# MCU_IO.net
KiCad netlist of a schematic drawn in Altium Designer
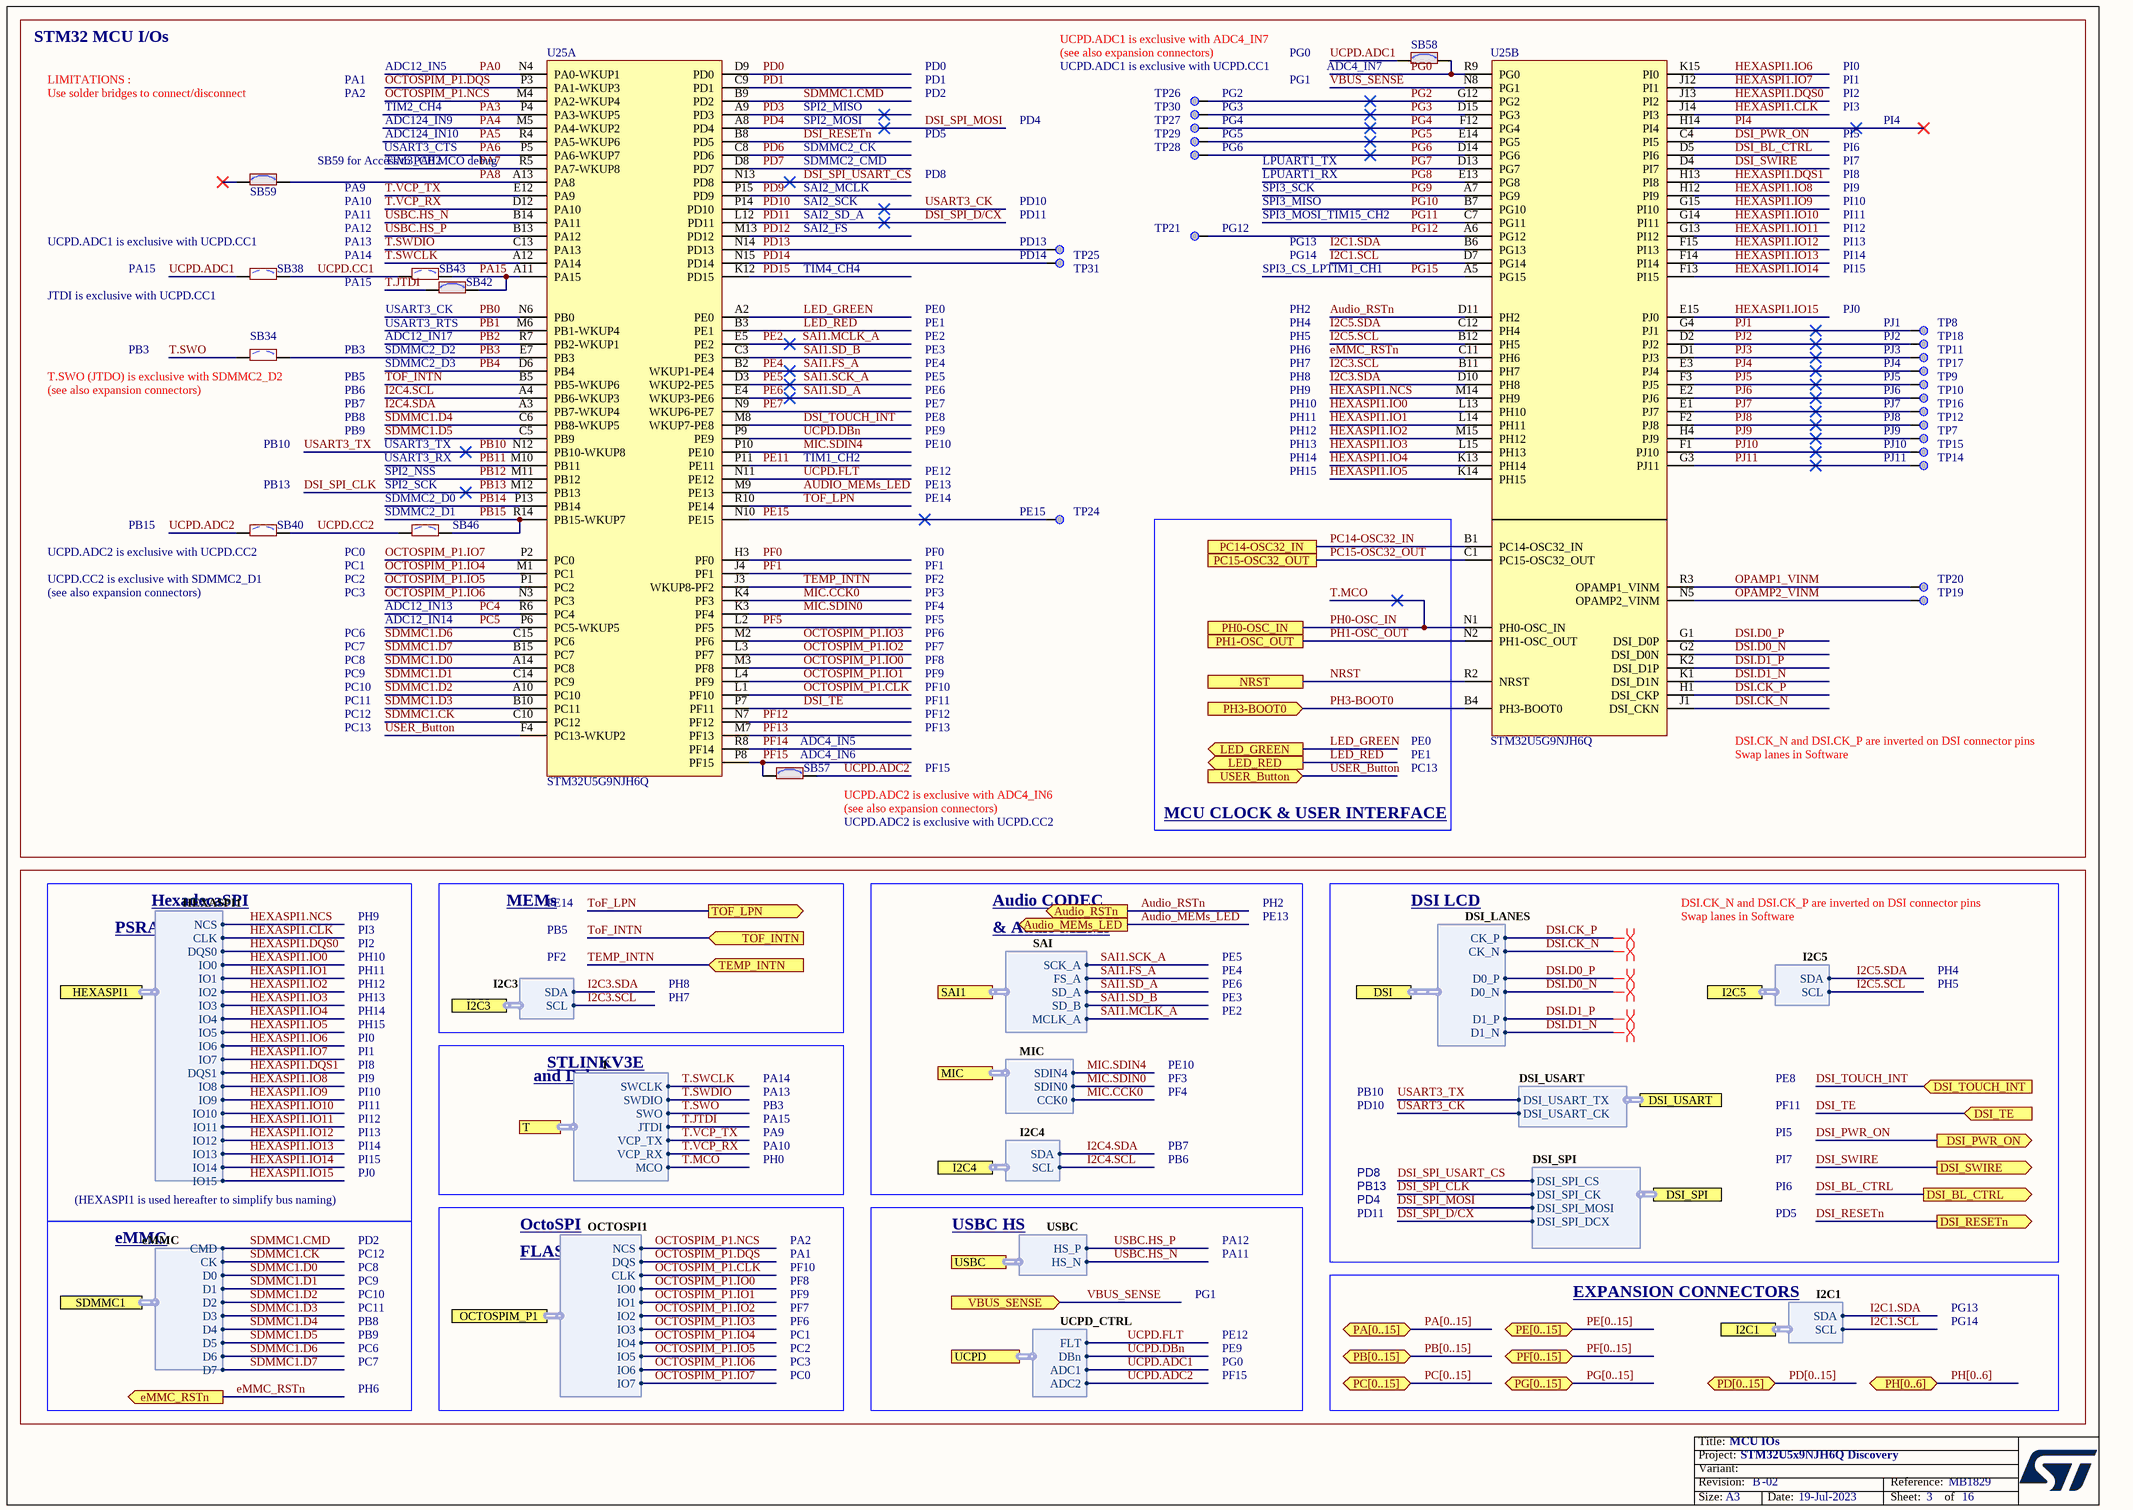
[diagram p0: MCU_IO.SchDoc]

(export (version "E")
  (design (tool "Eeschema 10.0.6"))
  (components
    (comp (ref "SB34")
      (value "SB_OFF")
      (footprint "MCD_PARTS:SOLDER-BRIDGE_R0402-0R")
      (description "Solder Bridge 0402 OFF")
      (fields
        (field (name "INTERNAL_PART_NUMBER") "MCD-02162")
        (field (name "MANUFACTURER_PART_NUMBER") "RC0402JR-070RL")
      )
      (libsource (lib "MCD_PARTS_database") (part "SB_OFF"))
    )
    (comp (ref "SB38")
      (value "SB_OFF")
      (footprint "MCD_PARTS:SOLDER-BRIDGE_R0402-0R")
      (description "Solder Bridge 0402 OFF")
      (fields
        (field (name "INTERNAL_PART_NUMBER") "MCD-02162")
        (field (name "MANUFACTURER_PART_NUMBER") "RC0402JR-070RL")
      )
      (libsource (lib "MCD_PARTS_database") (part "SB_OFF"))
    )
    (comp (ref "SB40")
      (value "SB_OFF")
      (footprint "MCD_PARTS:SOLDER-BRIDGE_R0402-0R")
      (description "Solder Bridge 0402 OFF")
      (fields
        (field (name "INTERNAL_PART_NUMBER") "MCD-02162")
        (field (name "MANUFACTURER_PART_NUMBER") "RC0402JR-070RL")
      )
      (libsource (lib "MCD_PARTS_database") (part "SB_OFF"))
    )
    (comp (ref "SB42")
      (value "SB_ON")
      (footprint "MCD_PARTS:SOLDER-BRIDGE_R0402-0R")
      (description "Solder Bridge 0402 ON")
      (fields
        (field (name "INTERNAL_PART_NUMBER") "MCD-01618")
        (field (name "MANUFACTURER_PART_NUMBER") "RC0402JR-070RL")
      )
      (libsource (lib "MCD_PARTS_database") (part "SB_ON"))
    )
    (comp (ref "SB43")
      (value "SB_OFF")
      (footprint "MCD_PARTS:SOLDER-BRIDGE_R0402-0R")
      (description "Solder Bridge 0402 OFF")
      (fields
        (field (name "INTERNAL_PART_NUMBER") "MCD-02162")
        (field (name "MANUFACTURER_PART_NUMBER") "RC0402JR-070RL")
      )
      (libsource (lib "MCD_PARTS_database") (part "SB_OFF"))
    )
    (comp (ref "SB46")
      (value "SB_OFF")
      (footprint "MCD_PARTS:SOLDER-BRIDGE_R0402-0R")
      (description "Solder Bridge 0402 OFF")
      (fields
        (field (name "INTERNAL_PART_NUMBER") "MCD-02162")
        (field (name "MANUFACTURER_PART_NUMBER") "RC0402JR-070RL")
      )
      (libsource (lib "MCD_PARTS_database") (part "SB_OFF"))
    )
    (comp (ref "SB57")
      (value "SB_ON")
      (footprint "MCD_PARTS:SOLDER-BRIDGE_R0402-0R")
      (description "Solder Bridge 0402 ON")
      (fields
        (field (name "INTERNAL_PART_NUMBER") "MCD-01618")
        (field (name "MANUFACTURER_PART_NUMBER") "RC0402JR-070RL")
      )
      (libsource (lib "MCD_PARTS_database") (part "SB_ON"))
    )
    (comp (ref "SB58")
      (value "SB_ON")
      (footprint "MCD_PARTS:SOLDER-BRIDGE_R0402-0R")
      (description "Solder Bridge 0402 ON")
      (fields
        (field (name "INTERNAL_PART_NUMBER") "MCD-01618")
        (field (name "MANUFACTURER_PART_NUMBER") "RC0402JR-070RL")
      )
      (libsource (lib "MCD_PARTS_database") (part "SB_ON"))
    )
    (comp (ref "SB59")
      (value "SB_ON")
      (footprint "MCD_PARTS:SOLDER-BRIDGE_R0402-0R")
      (description "Solder Bridge 0402 ON")
      (fields
        (field (name "INTERNAL_PART_NUMBER") "MCD-01618")
        (field (name "MANUFACTURER_PART_NUMBER") "RC0402JR-070RL")
      )
      (libsource (lib "MCD_PARTS_database") (part "SB_ON"))
    )
    (comp (ref "TP7")
      (value "Test Point")
      (footprint "MCD_PARTS:TP_SMD_1MM")
      (description "Test Point 1mm")
      (fields (field (name "INTERNAL_PART_NUMBER") "MCD-00074"))
      (libsource (lib "MCD_PARTS_database") (part "Test Point"))
    )
    (comp (ref "TP8")
      (value "Test Point")
      (footprint "MCD_PARTS:TP_SMD_1MM")
      (description "Test Point 1mm")
      (fields (field (name "INTERNAL_PART_NUMBER") "MCD-00074"))
      (libsource (lib "MCD_PARTS_database") (part "Test Point"))
    )
    (comp (ref "TP9")
      (value "Test Point")
      (footprint "MCD_PARTS:TP_SMD_1MM")
      (description "Test Point 1mm")
      (fields (field (name "INTERNAL_PART_NUMBER") "MCD-00074"))
      (libsource (lib "MCD_PARTS_database") (part "Test Point"))
    )
    (comp (ref "TP10")
      (value "Test Point")
      (footprint "MCD_PARTS:TP_SMD_1MM")
      (description "Test Point 1mm")
      (fields (field (name "INTERNAL_PART_NUMBER") "MCD-00074"))
      (libsource (lib "MCD_PARTS_database") (part "Test Point"))
    )
    (comp (ref "TP11")
      (value "Test Point")
      (footprint "MCD_PARTS:TP_SMD_1MM")
      (description "Test Point 1mm")
      (fields (field (name "INTERNAL_PART_NUMBER") "MCD-00074"))
      (libsource (lib "MCD_PARTS_database") (part "Test Point"))
    )
    (comp (ref "TP12")
      (value "Test Point")
      (footprint "MCD_PARTS:TP_SMD_1MM")
      (description "Test Point 1mm")
      (fields (field (name "INTERNAL_PART_NUMBER") "MCD-00074"))
      (libsource (lib "MCD_PARTS_database") (part "Test Point"))
    )
    (comp (ref "TP14")
      (value "Test Point")
      (footprint "MCD_PARTS:TP_SMD_1MM")
      (description "Test Point 1mm")
      (fields (field (name "INTERNAL_PART_NUMBER") "MCD-00074"))
      (libsource (lib "MCD_PARTS_database") (part "Test Point"))
    )
    (comp (ref "TP15")
      (value "Test Point")
      (footprint "MCD_PARTS:TP_SMD_1MM")
      (description "Test Point 1mm")
      (fields (field (name "INTERNAL_PART_NUMBER") "MCD-00074"))
      (libsource (lib "MCD_PARTS_database") (part "Test Point"))
    )
    (comp (ref "TP16")
      (value "Test Point")
      (footprint "MCD_PARTS:TP_SMD_1MM")
      (description "Test Point 1mm")
      (fields (field (name "INTERNAL_PART_NUMBER") "MCD-00074"))
      (libsource (lib "MCD_PARTS_database") (part "Test Point"))
    )
    (comp (ref "TP17")
      (value "Test Point")
      (footprint "MCD_PARTS:TP_SMD_1MM")
      (description "Test Point 1mm")
      (fields (field (name "INTERNAL_PART_NUMBER") "MCD-00074"))
      (libsource (lib "MCD_PARTS_database") (part "Test Point"))
    )
    (comp (ref "TP18")
      (value "Test Point")
      (footprint "MCD_PARTS:TP_SMD_1MM")
      (description "Test Point 1mm")
      (fields (field (name "INTERNAL_PART_NUMBER") "MCD-00074"))
      (libsource (lib "MCD_PARTS_database") (part "Test Point"))
    )
    (comp (ref "TP19")
      (value "Test Point")
      (footprint "MCD_PARTS:TP_SMD_1MM")
      (description "Test Point 1mm")
      (fields (field (name "INTERNAL_PART_NUMBER") "MCD-00074"))
      (libsource (lib "MCD_PARTS_database") (part "Test Point"))
    )
    (comp (ref "TP20")
      (value "Test Point")
      (footprint "MCD_PARTS:TP_SMD_1MM")
      (description "Test Point 1mm")
      (fields (field (name "INTERNAL_PART_NUMBER") "MCD-00074"))
      (libsource (lib "MCD_PARTS_database") (part "Test Point"))
    )
    (comp (ref "TP21")
      (value "Test Point")
      (footprint "MCD_PARTS:TP_SMD_1MM")
      (description "Test Point 1mm")
      (fields (field (name "INTERNAL_PART_NUMBER") "MCD-00074"))
      (libsource (lib "") (part "Test Point_1"))
    )
    (comp (ref "TP24")
      (value "Test Point")
      (footprint "MCD_PARTS:TP_SMD_1MM")
      (description "Test Point 1mm")
      (fields (field (name "INTERNAL_PART_NUMBER") "MCD-00074"))
      (libsource (lib "MCD_PARTS_database") (part "Test Point"))
    )
    (comp (ref "TP25")
      (value "Test Point")
      (footprint "MCD_PARTS:TP_SMD_1MM")
      (description "Test Point 1mm")
      (fields (field (name "INTERNAL_PART_NUMBER") "MCD-00074"))
      (libsource (lib "MCD_PARTS_database") (part "Test Point"))
    )
    (comp (ref "TP26")
      (value "Test Point")
      (footprint "MCD_PARTS:TP_SMD_1MM")
      (description "Test Point 1mm")
      (fields (field (name "INTERNAL_PART_NUMBER") "MCD-00074"))
      (libsource (lib "") (part "Test Point_1"))
    )
    (comp (ref "TP27")
      (value "Test Point")
      (footprint "MCD_PARTS:TP_SMD_1MM")
      (description "Test Point 1mm")
      (fields (field (name "INTERNAL_PART_NUMBER") "MCD-00074"))
      (libsource (lib "") (part "Test Point_1"))
    )
    (comp (ref "TP28")
      (value "Test Point")
      (footprint "MCD_PARTS:TP_SMD_1MM")
      (description "Test Point 1mm")
      (fields (field (name "INTERNAL_PART_NUMBER") "MCD-00074"))
      (libsource (lib "") (part "Test Point_1"))
    )
    (comp (ref "TP29")
      (value "Test Point")
      (footprint "MCD_PARTS:TP_SMD_1MM")
      (description "Test Point 1mm")
      (fields (field (name "INTERNAL_PART_NUMBER") "MCD-00074"))
      (libsource (lib "") (part "Test Point_1"))
    )
    (comp (ref "TP30")
      (value "Test Point")
      (footprint "MCD_PARTS:TP_SMD_1MM")
      (description "Test Point 1mm")
      (fields (field (name "INTERNAL_PART_NUMBER") "MCD-00074"))
      (libsource (lib "") (part "Test Point_1"))
    )
    (comp (ref "TP31")
      (value "Test Point")
      (footprint "MCD_PARTS:TP_SMD_1MM")
      (description "Test Point 1mm")
      (fields (field (name "INTERNAL_PART_NUMBER") "MCD-00074"))
      (libsource (lib "MCD_PARTS_database") (part "Test Point"))
    )
    (comp (ref "U25")
      (value "STM32U5G9NJH6Q")
      (footprint "ICC_TFBGA216_13X13_P080_H1P10_CODE-A0L2")
      (description "MCU, ARM Cortex-M33, 4MB Flash, 3MB RAM, With Crypto")
      (fields
        (field (name "INTERNAL_PART_NUMBER") "MCD-03271")
        (field (name "MANUFACTURER") "STMICROELECTRONICS")
      )
      (libsource (lib "MCD_PARTS_database") (part "STM32U599NJH6Q_BGA216_SMPS"))
    )
  )
  (nets
    (net (code "74") (name "/AUDIO_MEMs_LED") (class "Default")
      (node (ref "U25") (pin "M9") (pinfunction "PE13_M9") (pintype "passive"))
    )
    (net (code "76") (name "/Audio_RSTn") (class "Default")
      (node (ref "U25") (pin "D11") (pinfunction "PH2_D11") (pintype "passive"))
    )
    (net (code "77") (name "/DSI.CK_N") (class "Default")
      (node (ref "U25") (pin "J1") (pinfunction "DSI_CKN_J1") (pintype "passive"))
    )
    (net (code "78") (name "/DSI.CK_P") (class "Default")
      (node (ref "U25") (pin "H1") (pinfunction "DSI_CKP_H1") (pintype "passive"))
    )
    (net (code "79") (name "/DSI.D0_N") (class "Default")
      (node (ref "U25") (pin "G2") (pinfunction "DSI_D0N_G2") (pintype "passive"))
    )
    (net (code "80") (name "/DSI.D0_P") (class "Default")
      (node (ref "U25") (pin "G1") (pinfunction "DSI_D0P_G1") (pintype "passive"))
    )
    (net (code "81") (name "/DSI.D1_N") (class "Default")
      (node (ref "U25") (pin "K1") (pinfunction "DSI_D1N_K1") (pintype "passive"))
    )
    (net (code "82") (name "/DSI.D1_P") (class "Default")
      (node (ref "U25") (pin "K2") (pinfunction "DSI_D1P_K2") (pintype "passive"))
    )
    (net (code "83") (name "/DSI_BL_CTRL") (class "Default")
      (node (ref "U25") (pin "D5") (pinfunction "PI6_D5") (pintype "passive"))
    )
    (net (code "84") (name "/DSI_PWR_ON") (class "Default")
      (node (ref "U25") (pin "C4") (pinfunction "PI5_C4") (pintype "passive"))
    )
    (net (code "85") (name "/DSI_RESETn") (class "Default")
      (node (ref "U25") (pin "B8") (pinfunction "PD5_B8") (pintype "passive"))
    )
    (net (code "86") (name "/DSI_SPI_USART_CS") (class "Default")
      (node (ref "U25") (pin "N13") (pinfunction "PD8_N13") (pintype "passive"))
    )
    (net (code "87") (name "/DSI_SWIRE") (class "Default")
      (node (ref "U25") (pin "D4") (pinfunction "PI7_D4") (pintype "passive"))
    )
    (net (code "88") (name "/DSI_TE") (class "Default")
      (node (ref "U25") (pin "P7") (pinfunction "PF11_P7") (pintype "passive"))
    )
    (net (code "89") (name "/DSI_TOUCH_INT") (class "Default")
      (node (ref "U25") (pin "M8") (pinfunction "WKUP7-PE8_M8") (pintype "passive"))
    )
    (net (code "90") (name "/HEXASPI1.CLK") (class "Default")
      (node (ref "U25") (pin "J14") (pinfunction "PI3_J14") (pintype "passive"))
    )
    (net (code "91") (name "/HEXASPI1.DQS0") (class "Default")
      (node (ref "U25") (pin "J13") (pinfunction "PI2_J13") (pintype "passive"))
    )
    (net (code "92") (name "/HEXASPI1.DQS1") (class "Default")
      (node (ref "U25") (pin "H13") (pinfunction "PI8_H13") (pintype "passive"))
    )
    (net (code "93") (name "/HEXASPI1.IO0") (class "Default")
      (node (ref "U25") (pin "L13") (pinfunction "PH10_L13") (pintype "passive"))
    )
    (net (code "94") (name "/HEXASPI1.IO1") (class "Default")
      (node (ref "U25") (pin "L14") (pinfunction "PH11_L14") (pintype "passive"))
    )
    (net (code "95") (name "/HEXASPI1.IO2") (class "Default")
      (node (ref "U25") (pin "M15") (pinfunction "PH12_M15") (pintype "passive"))
    )
    (net (code "96") (name "/HEXASPI1.IO3") (class "Default")
      (node (ref "U25") (pin "L15") (pinfunction "PH13_L15") (pintype "passive"))
    )
    (net (code "97") (name "/HEXASPI1.IO4") (class "Default")
      (node (ref "U25") (pin "K13") (pinfunction "PH14_K13") (pintype "passive"))
    )
    (net (code "98") (name "/HEXASPI1.IO5") (class "Default")
      (node (ref "U25") (pin "K14") (pinfunction "PH15_K14") (pintype "passive"))
    )
    (net (code "99") (name "/HEXASPI1.IO6") (class "Default")
      (node (ref "U25") (pin "K15") (pinfunction "PI0_K15") (pintype "passive"))
    )
    (net (code "100") (name "/HEXASPI1.IO7") (class "Default")
      (node (ref "U25") (pin "J12") (pinfunction "PI1_J12") (pintype "passive"))
    )
    (net (code "101") (name "/HEXASPI1.IO8") (class "Default")
      (node (ref "U25") (pin "H12") (pinfunction "PI9_H12") (pintype "passive"))
    )
    (net (code "102") (name "/HEXASPI1.IO9") (class "Default")
      (node (ref "U25") (pin "G15") (pinfunction "PI10_G15") (pintype "passive"))
    )
    (net (code "103") (name "/HEXASPI1.IO10") (class "Default")
      (node (ref "U25") (pin "G14") (pinfunction "PI11_G14") (pintype "passive"))
    )
    (net (code "104") (name "/HEXASPI1.IO11") (class "Default")
      (node (ref "U25") (pin "G13") (pinfunction "PI12_G13") (pintype "passive"))
    )
    (net (code "105") (name "/HEXASPI1.IO12") (class "Default")
      (node (ref "U25") (pin "F15") (pinfunction "PI13_F15") (pintype "passive"))
    )
    (net (code "106") (name "/HEXASPI1.IO13") (class "Default")
      (node (ref "U25") (pin "F14") (pinfunction "PI14_F14") (pintype "passive"))
    )
    (net (code "107") (name "/HEXASPI1.IO14") (class "Default")
      (node (ref "U25") (pin "F13") (pinfunction "PI15_F13") (pintype "passive"))
    )
    (net (code "108") (name "/HEXASPI1.IO15") (class "Default")
      (node (ref "U25") (pin "E15") (pinfunction "PJ0_E15") (pintype "passive"))
    )
    (net (code "109") (name "/HEXASPI1.NCS") (class "Default")
      (node (ref "U25") (pin "M14") (pinfunction "PH9_M14") (pintype "passive"))
    )
    (net (code "110") (name "/I2C1.SCL") (class "Default")
      (node (ref "U25") (pin "D7") (pinfunction "PG14_D7") (pintype "passive"))
    )
    (net (code "111") (name "/I2C1.SDA") (class "Default")
      (node (ref "U25") (pin "B6") (pinfunction "PG13_B6") (pintype "passive"))
    )
    (net (code "112") (name "/I2C3.SCL") (class "Default")
      (node (ref "U25") (pin "B11") (pinfunction "PH7_B11") (pintype "passive"))
    )
    (net (code "113") (name "/I2C3.SDA") (class "Default")
      (node (ref "U25") (pin "D10") (pinfunction "PH8_D10") (pintype "passive"))
    )
    (net (code "114") (name "/I2C4.SCL") (class "Default")
      (node (ref "U25") (pin "A4") (pinfunction "PB6-WKUP3_A4") (pintype "passive"))
    )
    (net (code "115") (name "/I2C4.SDA") (class "Default")
      (node (ref "U25") (pin "A3") (pinfunction "PB7-WKUP4_A3") (pintype "passive"))
    )
    (net (code "116") (name "/I2C5.SCL") (class "Default")
      (node (ref "U25") (pin "B12") (pinfunction "PH5_B12") (pintype "passive"))
    )
    (net (code "117") (name "/I2C5.SDA") (class "Default")
      (node (ref "U25") (pin "C12") (pinfunction "PH4_C12") (pintype "passive"))
    )
    (net (code "118") (name "/LED_GREEN") (class "Default")
      (node (ref "U25") (pin "A2") (pinfunction "PE0_A2") (pintype "passive"))
    )
    (net (code "119") (name "/LED_RED") (class "Default")
      (node (ref "U25") (pin "B3") (pinfunction "PE1_B3") (pintype "passive"))
    )
    (net (code "120") (name "/MIC.CCK0") (class "Default")
      (node (ref "U25") (pin "K4") (pinfunction "PF3_K4") (pintype "passive"))
    )
    (net (code "121") (name "/MIC.SDIN0") (class "Default")
      (node (ref "U25") (pin "K3") (pinfunction "PF4_K3") (pintype "passive"))
    )
    (net (code "122") (name "/MIC.SDIN4") (class "Default")
      (node (ref "U25") (pin "P10") (pinfunction "PE10_P10") (pintype "passive"))
    )
    (net (code "123") (name "/NRST") (class "Default")
      (node (ref "U25") (pin "R2") (pinfunction "NRST_R2") (pintype "passive"))
    )
    (net (code "124") (name "/OCTOSPIM_P1.CLK") (class "Default")
      (node (ref "U25") (pin "L1") (pinfunction "PF10_L1") (pintype "passive"))
    )
    (net (code "125") (name "/OCTOSPIM_P1.DQS") (class "Default")
      (node (ref "U25") (pin "P3") (pinfunction "PA1-WKUP3_P3") (pintype "passive"))
    )
    (net (code "126") (name "/OCTOSPIM_P1.IO0") (class "Default")
      (node (ref "U25") (pin "M3") (pinfunction "PF8_M3") (pintype "passive"))
    )
    (net (code "127") (name "/OCTOSPIM_P1.IO1") (class "Default")
      (node (ref "U25") (pin "L4") (pinfunction "PF9_L4") (pintype "passive"))
    )
    (net (code "128") (name "/OCTOSPIM_P1.IO2") (class "Default")
      (node (ref "U25") (pin "L3") (pinfunction "PF7_L3") (pintype "passive"))
    )
    (net (code "129") (name "/OCTOSPIM_P1.IO3") (class "Default")
      (node (ref "U25") (pin "M2") (pinfunction "PF6_M2") (pintype "passive"))
    )
    (net (code "130") (name "/OCTOSPIM_P1.IO4") (class "Default")
      (node (ref "U25") (pin "M1") (pinfunction "PC1_M1") (pintype "passive"))
    )
    (net (code "131") (name "/OCTOSPIM_P1.IO5") (class "Default")
      (node (ref "U25") (pin "P1") (pinfunction "PC2_P1") (pintype "passive"))
    )
    (net (code "132") (name "/OCTOSPIM_P1.IO6") (class "Default")
      (node (ref "U25") (pin "N3") (pinfunction "PC3_N3") (pintype "passive"))
    )
    (net (code "133") (name "/OCTOSPIM_P1.IO7") (class "Default")
      (node (ref "U25") (pin "P2") (pinfunction "PC0_P2") (pintype "passive"))
    )
    (net (code "134") (name "/OCTOSPIM_P1.NCS") (class "Default")
      (node (ref "U25") (pin "M4") (pinfunction "PA2-WKUP4_M4") (pintype "passive"))
    )
    (net (code "135") (name "/OPAMP1_VINM") (class "Default")
      (node (ref "TP20") (pin "1") (pinfunction "1_1") (pintype "passive"))
      (node (ref "U25") (pin "R3") (pinfunction "OPAMP1_VINM_R3") (pintype "passive"))
    )
    (net (code "136") (name "/OPAMP2_VINM") (class "Default")
      (node (ref "TP19") (pin "1") (pinfunction "1_1") (pintype "passive"))
      (node (ref "U25") (pin "N5") (pinfunction "OPAMP2_VINM_N5") (pintype "passive"))
    )
    (net (code "137") (name "/PA0") (class "Default")
      (node (ref "U25") (pin "N4") (pinfunction "PA0-WKUP1_N4") (pintype "passive"))
    )
    (net (code "138") (name "/PA3") (class "Default")
      (node (ref "U25") (pin "P4") (pinfunction "PA3-WKUP5_P4") (pintype "passive"))
    )
    (net (code "139") (name "/PA4") (class "Default")
      (node (ref "U25") (pin "M5") (pinfunction "PA4-WKUP2_M5") (pintype "passive"))
    )
    (net (code "140") (name "/PA5") (class "Default")
      (node (ref "U25") (pin "R4") (pinfunction "PA5-WKUP6_R4") (pintype "passive"))
    )
    (net (code "141") (name "/PA6") (class "Default")
      (node (ref "U25") (pin "P5") (pinfunction "PA6-WKUP7_P5") (pintype "passive"))
    )
    (net (code "142") (name "/PA7") (class "Default")
      (node (ref "U25") (pin "R5") (pinfunction "PA7-WKUP8_R5") (pintype "passive"))
    )
    (net (code "143") (name "/PA8") (class "Default")
      (node (ref "SB59") (pin "2") (pinfunction "2_2") (pintype "passive"))
      (node (ref "U25") (pin "A13") (pinfunction "PA8_A13") (pintype "passive"))
    )
    (net (code "144") (name "/PA15") (class "Default")
      (node (ref "SB42") (pin "2") (pinfunction "2_2") (pintype "passive"))
      (node (ref "SB43") (pin "2") (pinfunction "2_2") (pintype "passive"))
      (node (ref "U25") (pin "A11") (pinfunction "PA15_A11") (pintype "passive"))
    )
    (net (code "146") (name "/PB0") (class "Default")
      (node (ref "U25") (pin "N6") (pinfunction "PB0_N6") (pintype "passive"))
    )
    (net (code "147") (name "/PB1") (class "Default")
      (node (ref "U25") (pin "M6") (pinfunction "PB1-WKUP4_M6") (pintype "passive"))
    )
    (net (code "148") (name "/PB2") (class "Default")
      (node (ref "U25") (pin "R7") (pinfunction "PB2-WKUP1_R7") (pintype "passive"))
    )
    (net (code "149") (name "/PB3") (class "Default")
      (node (ref "SB34") (pin "2") (pinfunction "2_2") (pintype "passive"))
      (node (ref "U25") (pin "E7") (pinfunction "PB3_E7") (pintype "passive"))
    )
    (net (code "150") (name "/PB4") (class "Default")
      (node (ref "U25") (pin "D6") (pinfunction "PB4_D6") (pintype "passive"))
    )
    (net (code "151") (name "/PB10") (class "Default")
      (node (ref "U25") (pin "N12") (pinfunction "PB10-WKUP8_N12") (pintype "passive"))
    )
    (net (code "152") (name "/PB11") (class "Default")
      (node (ref "U25") (pin "M10") (pinfunction "PB11_M10") (pintype "passive"))
    )
    (net (code "153") (name "/PB12") (class "Default")
      (node (ref "U25") (pin "M11") (pinfunction "PB12_M11") (pintype "passive"))
    )
    (net (code "154") (name "/PB13") (class "Default")
      (node (ref "U25") (pin "M12") (pinfunction "PB13_M12") (pintype "passive"))
    )
    (net (code "155") (name "/PB14") (class "Default")
      (node (ref "U25") (pin "P13") (pinfunction "PB14_P13") (pintype "passive"))
    )
    (net (code "156") (name "/PB15") (class "Default")
      (node (ref "SB46") (pin "2") (pinfunction "2_2") (pintype "passive"))
      (node (ref "U25") (pin "R14") (pinfunction "PB15-WKUP7_R14") (pintype "passive"))
    )
    (net (code "158") (name "/PC4") (class "Default")
      (node (ref "U25") (pin "R6") (pinfunction "PC4_R6") (pintype "passive"))
    )
    (net (code "159") (name "/PC5") (class "Default")
      (node (ref "U25") (pin "P6") (pinfunction "PC5-WKUP5_P6") (pintype "passive"))
    )
    (net (code "160") (name "/PC14-OSC32_IN") (class "Default")
      (node (ref "U25") (pin "B1") (pinfunction "PC14-OSC32_IN_B1") (pintype "passive"))
    )
    (net (code "161") (name "/PC15-OSC32_OUT") (class "Default")
      (node (ref "U25") (pin "C1") (pinfunction "PC15-OSC32_OUT_C1") (pintype "passive"))
    )
    (net (code "163") (name "/PD0") (class "Default")
      (node (ref "U25") (pin "D9") (pinfunction "PD0_D9") (pintype "passive"))
    )
    (net (code "164") (name "/PD1") (class "Default")
      (node (ref "U25") (pin "C9") (pinfunction "PD1_C9") (pintype "passive"))
    )
    (net (code "165") (name "/PD3") (class "Default")
      (node (ref "U25") (pin "A9") (pinfunction "PD3_A9") (pintype "passive"))
    )
    (net (code "166") (name "/PD4") (class "Default")
      (node (ref "U25") (pin "A8") (pinfunction "PD4_A8") (pintype "passive"))
    )
    (net (code "167") (name "/PD6") (class "Default")
      (node (ref "U25") (pin "C8") (pinfunction "PD6_C8") (pintype "passive"))
    )
    (net (code "168") (name "/PD7") (class "Default")
      (node (ref "U25") (pin "D8") (pinfunction "PD7_D8") (pintype "passive"))
    )
    (net (code "169") (name "/PD9") (class "Default")
      (node (ref "U25") (pin "P15") (pinfunction "PD9_P15") (pintype "passive"))
    )
    (net (code "170") (name "/PD10") (class "Default")
      (node (ref "U25") (pin "P14") (pinfunction "PD10_P14") (pintype "passive"))
    )
    (net (code "171") (name "/PD11") (class "Default")
      (node (ref "U25") (pin "L12") (pinfunction "PD11_L12") (pintype "passive"))
    )
    (net (code "172") (name "/PD12") (class "Default")
      (node (ref "U25") (pin "M13") (pinfunction "PD12_M13") (pintype "passive"))
    )
    (net (code "173") (name "/PD13") (class "Default")
      (node (ref "TP25") (pin "1") (pinfunction "1_1") (pintype "passive"))
      (node (ref "U25") (pin "N14") (pinfunction "PD13_N14") (pintype "passive"))
    )
    (net (code "174") (name "/PD14") (class "Default")
      (node (ref "TP31") (pin "1") (pinfunction "1_1") (pintype "passive"))
      (node (ref "U25") (pin "N15") (pinfunction "PD14_N15") (pintype "passive"))
    )
    (net (code "175") (name "/PD15") (class "Default")
      (node (ref "U25") (pin "K12") (pinfunction "PD15_K12") (pintype "passive"))
    )
    (net (code "177") (name "/PE2") (class "Default")
      (node (ref "U25") (pin "E5") (pinfunction "PE2_E5") (pintype "passive"))
    )
    (net (code "178") (name "/PE4") (class "Default")
      (node (ref "U25") (pin "B2") (pinfunction "WKUP1-PE4_B2") (pintype "passive"))
    )
    (net (code "179") (name "/PE5") (class "Default")
      (node (ref "U25") (pin "D3") (pinfunction "WKUP2-PE5_D3") (pintype "passive"))
    )
    (net (code "180") (name "/PE6") (class "Default")
      (node (ref "U25") (pin "E4") (pinfunction "WKUP3-PE6_E4") (pintype "passive"))
    )
    (net (code "181") (name "/PE7") (class "Default")
      (node (ref "U25") (pin "N9") (pinfunction "WKUP6-PE7_N9") (pintype "passive"))
    )
    (net (code "182") (name "/PE11") (class "Default")
      (node (ref "U25") (pin "P11") (pinfunction "PE11_P11") (pintype "passive"))
    )
    (net (code "183") (name "/PE15") (class "Default")
      (node (ref "TP24") (pin "1") (pinfunction "1_1") (pintype "passive"))
      (node (ref "U25") (pin "N10") (pinfunction "PE15_N10") (pintype "passive"))
    )
    (net (code "185") (name "/PF0") (class "Default")
      (node (ref "U25") (pin "H3") (pinfunction "PF0_H3") (pintype "passive"))
    )
    (net (code "186") (name "/PF1") (class "Default")
      (node (ref "U25") (pin "J4") (pinfunction "PF1_J4") (pintype "passive"))
    )
    (net (code "187") (name "/PF5") (class "Default")
      (node (ref "U25") (pin "L2") (pinfunction "PF5_L2") (pintype "passive"))
    )
    (net (code "188") (name "/PF12") (class "Default")
      (node (ref "U25") (pin "N7") (pinfunction "PF12_N7") (pintype "passive"))
    )
    (net (code "189") (name "/PF13") (class "Default")
      (node (ref "U25") (pin "M7") (pinfunction "PF13_M7") (pintype "passive"))
    )
    (net (code "190") (name "/PF14") (class "Default")
      (node (ref "U25") (pin "R8") (pinfunction "PF14_R8") (pintype "passive"))
    )
    (net (code "191") (name "/PF15") (class "Default")
      (node (ref "SB57") (pin "1") (pinfunction "1_1") (pintype "passive"))
      (node (ref "U25") (pin "P8") (pinfunction "PF15_P8") (pintype "passive"))
    )
    (net (code "193") (name "/PG0") (class "Default")
      (node (ref "SB58") (pin "2") (pinfunction "2_2") (pintype "passive"))
      (node (ref "U25") (pin "R9") (pinfunction "PG0_R9") (pintype "passive"))
    )
    (net (code "194") (name "/PG2") (class "Default")
      (node (ref "TP26") (pin "1") (pinfunction "1_1") (pintype "passive"))
      (node (ref "U25") (pin "G12") (pinfunction "PG2_G12") (pintype "passive"))
    )
    (net (code "195") (name "/PG3") (class "Default")
      (node (ref "TP30") (pin "1") (pinfunction "1_1") (pintype "passive"))
      (node (ref "U25") (pin "D15") (pinfunction "PG3_D15") (pintype "passive"))
    )
    (net (code "196") (name "/PG4") (class "Default")
      (node (ref "TP27") (pin "1") (pinfunction "1_1") (pintype "passive"))
      (node (ref "U25") (pin "F12") (pinfunction "PG4_F12") (pintype "passive"))
    )
    (net (code "197") (name "/PG5") (class "Default")
      (node (ref "TP29") (pin "1") (pinfunction "1_1") (pintype "passive"))
      (node (ref "U25") (pin "E14") (pinfunction "PG5_E14") (pintype "passive"))
    )
    (net (code "198") (name "/PG6") (class "Default")
      (node (ref "TP28") (pin "1") (pinfunction "1_1") (pintype "passive"))
      (node (ref "U25") (pin "D14") (pinfunction "PG6_D14") (pintype "passive"))
    )
    (net (code "199") (name "/PG7") (class "Default")
      (node (ref "U25") (pin "D13") (pinfunction "PG7_D13") (pintype "passive"))
    )
    (net (code "200") (name "/PG8") (class "Default")
      (node (ref "U25") (pin "E13") (pinfunction "PG8_E13") (pintype "passive"))
    )
    (net (code "201") (name "/PG9") (class "Default")
      (node (ref "U25") (pin "A7") (pinfunction "PG9_A7") (pintype "passive"))
    )
    (net (code "202") (name "/PG10") (class "Default")
      (node (ref "U25") (pin "B7") (pinfunction "PG10_B7") (pintype "passive"))
    )
    (net (code "203") (name "/PG11") (class "Default")
      (node (ref "U25") (pin "C7") (pinfunction "PG11_C7") (pintype "passive"))
    )
    (net (code "204") (name "/PG12") (class "Default")
      (node (ref "TP21") (pin "1") (pinfunction "1_1") (pintype "passive"))
      (node (ref "U25") (pin "A6") (pinfunction "PG12_A6") (pintype "passive"))
    )
    (net (code "205") (name "/PG15") (class "Default")
      (node (ref "U25") (pin "A5") (pinfunction "PG15_A5") (pintype "passive"))
    )
    (net (code "207") (name "/PH0-OSC_IN") (class "Default")
      (node (ref "U25") (pin "N1") (pinfunction "PH0-OSC_IN_N1") (pintype "passive"))
    )
    (net (code "208") (name "/PH1-OSC_OUT") (class "Default")
      (node (ref "U25") (pin "N2") (pinfunction "PH1-OSC_OUT_N2") (pintype "passive"))
    )
    (net (code "209") (name "/PH3-BOOT0") (class "Default")
      (node (ref "U25") (pin "B4") (pinfunction "PH3-BOOT0_B4") (pintype "passive"))
    )
    (net (code "211") (name "/PI4") (class "Default")
      (node (ref "U25") (pin "H14") (pinfunction "PI4_H14") (pintype "passive+no_connect"))
    )
    (net (code "212") (name "/PJ1") (class "Default")
      (node (ref "TP8") (pin "1") (pinfunction "1_1") (pintype "passive"))
      (node (ref "U25") (pin "G4") (pinfunction "PJ1_G4") (pintype "passive"))
    )
    (net (code "213") (name "/PJ2") (class "Default")
      (node (ref "TP18") (pin "1") (pinfunction "1_1") (pintype "passive"))
      (node (ref "U25") (pin "D2") (pinfunction "PJ2_D2") (pintype "passive"))
    )
    (net (code "214") (name "/PJ3") (class "Default")
      (node (ref "TP11") (pin "1") (pinfunction "1_1") (pintype "passive"))
      (node (ref "U25") (pin "D1") (pinfunction "PJ3_D1") (pintype "passive"))
    )
    (net (code "215") (name "/PJ4") (class "Default")
      (node (ref "TP17") (pin "1") (pinfunction "1_1") (pintype "passive"))
      (node (ref "U25") (pin "E3") (pinfunction "PJ4_E3") (pintype "passive"))
    )
    (net (code "216") (name "/PJ5") (class "Default")
      (node (ref "TP9") (pin "1") (pinfunction "1_1") (pintype "passive"))
      (node (ref "U25") (pin "F3") (pinfunction "PJ5_F3") (pintype "passive"))
    )
    (net (code "217") (name "/PJ6") (class "Default")
      (node (ref "TP10") (pin "1") (pinfunction "1_1") (pintype "passive"))
      (node (ref "U25") (pin "E2") (pinfunction "PJ6_E2") (pintype "passive"))
    )
    (net (code "218") (name "/PJ7") (class "Default")
      (node (ref "TP16") (pin "1") (pinfunction "1_1") (pintype "passive"))
      (node (ref "U25") (pin "E1") (pinfunction "PJ7_E1") (pintype "passive"))
    )
    (net (code "219") (name "/PJ8") (class "Default")
      (node (ref "TP12") (pin "1") (pinfunction "1_1") (pintype "passive"))
      (node (ref "U25") (pin "F2") (pinfunction "PJ8_F2") (pintype "passive"))
    )
    (net (code "220") (name "/PJ9") (class "Default")
      (node (ref "TP7") (pin "1") (pinfunction "1_1") (pintype "passive"))
      (node (ref "U25") (pin "H4") (pinfunction "PJ9_H4") (pintype "passive"))
    )
    (net (code "221") (name "/PJ10") (class "Default")
      (node (ref "TP15") (pin "1") (pinfunction "1_1") (pintype "passive"))
      (node (ref "U25") (pin "F1") (pinfunction "PJ10_F1") (pintype "passive"))
    )
    (net (code "222") (name "/PJ11") (class "Default")
      (node (ref "TP14") (pin "1") (pinfunction "1_1") (pintype "passive"))
      (node (ref "U25") (pin "G3") (pinfunction "PJ11_G3") (pintype "passive"))
    )
    (net (code "223") (name "/SAI1.SD_B") (class "Default")
      (node (ref "U25") (pin "C3") (pinfunction "PE3_C3") (pintype "passive"))
    )
    (net (code "224") (name "/SDMMC1.CK") (class "Default")
      (node (ref "U25") (pin "C10") (pinfunction "PC12_C10") (pintype "passive"))
    )
    (net (code "225") (name "/SDMMC1.CMD") (class "Default")
      (node (ref "U25") (pin "B9") (pinfunction "PD2_B9") (pintype "passive"))
    )
    (net (code "226") (name "/SDMMC1.D0") (class "Default")
      (node (ref "U25") (pin "A14") (pinfunction "PC8_A14") (pintype "passive"))
    )
    (net (code "227") (name "/SDMMC1.D1") (class "Default")
      (node (ref "U25") (pin "C14") (pinfunction "PC9_C14") (pintype "passive"))
    )
    (net (code "228") (name "/SDMMC1.D2") (class "Default")
      (node (ref "U25") (pin "A10") (pinfunction "PC10_A10") (pintype "passive"))
    )
    (net (code "229") (name "/SDMMC1.D3") (class "Default")
      (node (ref "U25") (pin "B10") (pinfunction "PC11_B10") (pintype "passive"))
    )
    (net (code "230") (name "/SDMMC1.D4") (class "Default")
      (node (ref "U25") (pin "C6") (pinfunction "PB8-WKUP5_C6") (pintype "passive"))
    )
    (net (code "231") (name "/SDMMC1.D5") (class "Default")
      (node (ref "U25") (pin "C5") (pinfunction "PB9_C5") (pintype "passive"))
    )
    (net (code "232") (name "/SDMMC1.D6") (class "Default")
      (node (ref "U25") (pin "C15") (pinfunction "PC6_C15") (pintype "passive"))
    )
    (net (code "233") (name "/SDMMC1.D7") (class "Default")
      (node (ref "U25") (pin "B15") (pinfunction "PC7_B15") (pintype "passive"))
    )
    (net (code "234") (name "/T.JTDI") (class "Default")
      (node (ref "SB42") (pin "1") (pinfunction "1_1") (pintype "passive"))
    )
    (net (code "235") (name "/T.SWCLK") (class "Default")
      (node (ref "U25") (pin "A12") (pinfunction "PA14_A12") (pintype "passive"))
    )
    (net (code "236") (name "/T.SWDIO") (class "Default")
      (node (ref "U25") (pin "C13") (pinfunction "PA13_C13") (pintype "passive"))
    )
    (net (code "237") (name "/T.SWO") (class "Default")
      (node (ref "SB34") (pin "1") (pinfunction "1_1") (pintype "passive"))
    )
    (net (code "238") (name "/T.VCP_RX") (class "Default")
      (node (ref "U25") (pin "D12") (pinfunction "PA10_D12") (pintype "passive"))
    )
    (net (code "239") (name "/T.VCP_TX") (class "Default")
      (node (ref "U25") (pin "E12") (pinfunction "PA9_E12") (pintype "passive"))
    )
    (net (code "240") (name "/TEMP_INTN") (class "Default")
      (node (ref "U25") (pin "J3") (pinfunction "WKUP8-PF2_J3") (pintype "passive"))
    )
    (net (code "241") (name "/TOF_INTN") (class "Default")
      (node (ref "U25") (pin "B5") (pinfunction "PB5-WKUP6_B5") (pintype "passive"))
    )
    (net (code "242") (name "/TOF_LPN") (class "Default")
      (node (ref "U25") (pin "R10") (pinfunction "PE14_R10") (pintype "passive"))
    )
    (net (code "243") (name "/UCPD.ADC1") (class "Default")
      (node (ref "SB38") (pin "1") (pinfunction "1_1") (pintype "passive"))
      (node (ref "SB58") (pin "1") (pinfunction "1_1") (pintype "passive"))
    )
    (net (code "244") (name "/UCPD.ADC2") (class "Default")
      (node (ref "SB40") (pin "1") (pinfunction "1_1") (pintype "passive"))
      (node (ref "SB57") (pin "2") (pinfunction "2_2") (pintype "passive"))
    )
    (net (code "245") (name "/UCPD.CC1") (class "Default")
      (node (ref "SB38") (pin "2") (pinfunction "2_2") (pintype "passive"))
      (node (ref "SB43") (pin "1") (pinfunction "1_1") (pintype "passive"))
    )
    (net (code "246") (name "/UCPD.CC2") (class "Default")
      (node (ref "SB40") (pin "2") (pinfunction "2_2") (pintype "passive"))
      (node (ref "SB46") (pin "1") (pinfunction "1_1") (pintype "passive"))
    )
    (net (code "247") (name "/UCPD.DBn") (class "Default")
      (node (ref "U25") (pin "P9") (pinfunction "PE9_P9") (pintype "passive"))
    )
    (net (code "248") (name "/UCPD.FLT") (class "Default")
      (node (ref "U25") (pin "N11") (pinfunction "PE12_N11") (pintype "passive"))
    )
    (net (code "249") (name "/USBC.HS_N") (class "Default")
      (node (ref "U25") (pin "B14") (pinfunction "PA11_B14") (pintype "passive"))
    )
    (net (code "250") (name "/USBC.HS_P") (class "Default")
      (node (ref "U25") (pin "B13") (pinfunction "PA12_B13") (pintype "passive"))
    )
    (net (code "251") (name "/USER_Button") (class "Default")
      (node (ref "U25") (pin "F4") (pinfunction "PC13-WKUP2_F4") (pintype "passive"))
    )
    (net (code "252") (name "/VBUS_SENSE") (class "Default")
      (node (ref "U25") (pin "N8") (pinfunction "PG1_N8") (pintype "passive"))
    )
    (net (code "253") (name "/eMMC_RSTn") (class "Default")
      (node (ref "U25") (pin "C11") (pinfunction "PH6_C11") (pintype "passive"))
    )
    (net (code "269") (name "unconnected-(SB59-Pad1)") (class "Default")
      (node (ref "SB59") (pin "1") (pinfunction "1_1") (pintype "passive+no_connect"))
    )
  )
)
